# 08_-PumpDriverUnit.net
KiCad netlist of a schematic drawn in Altium Designer
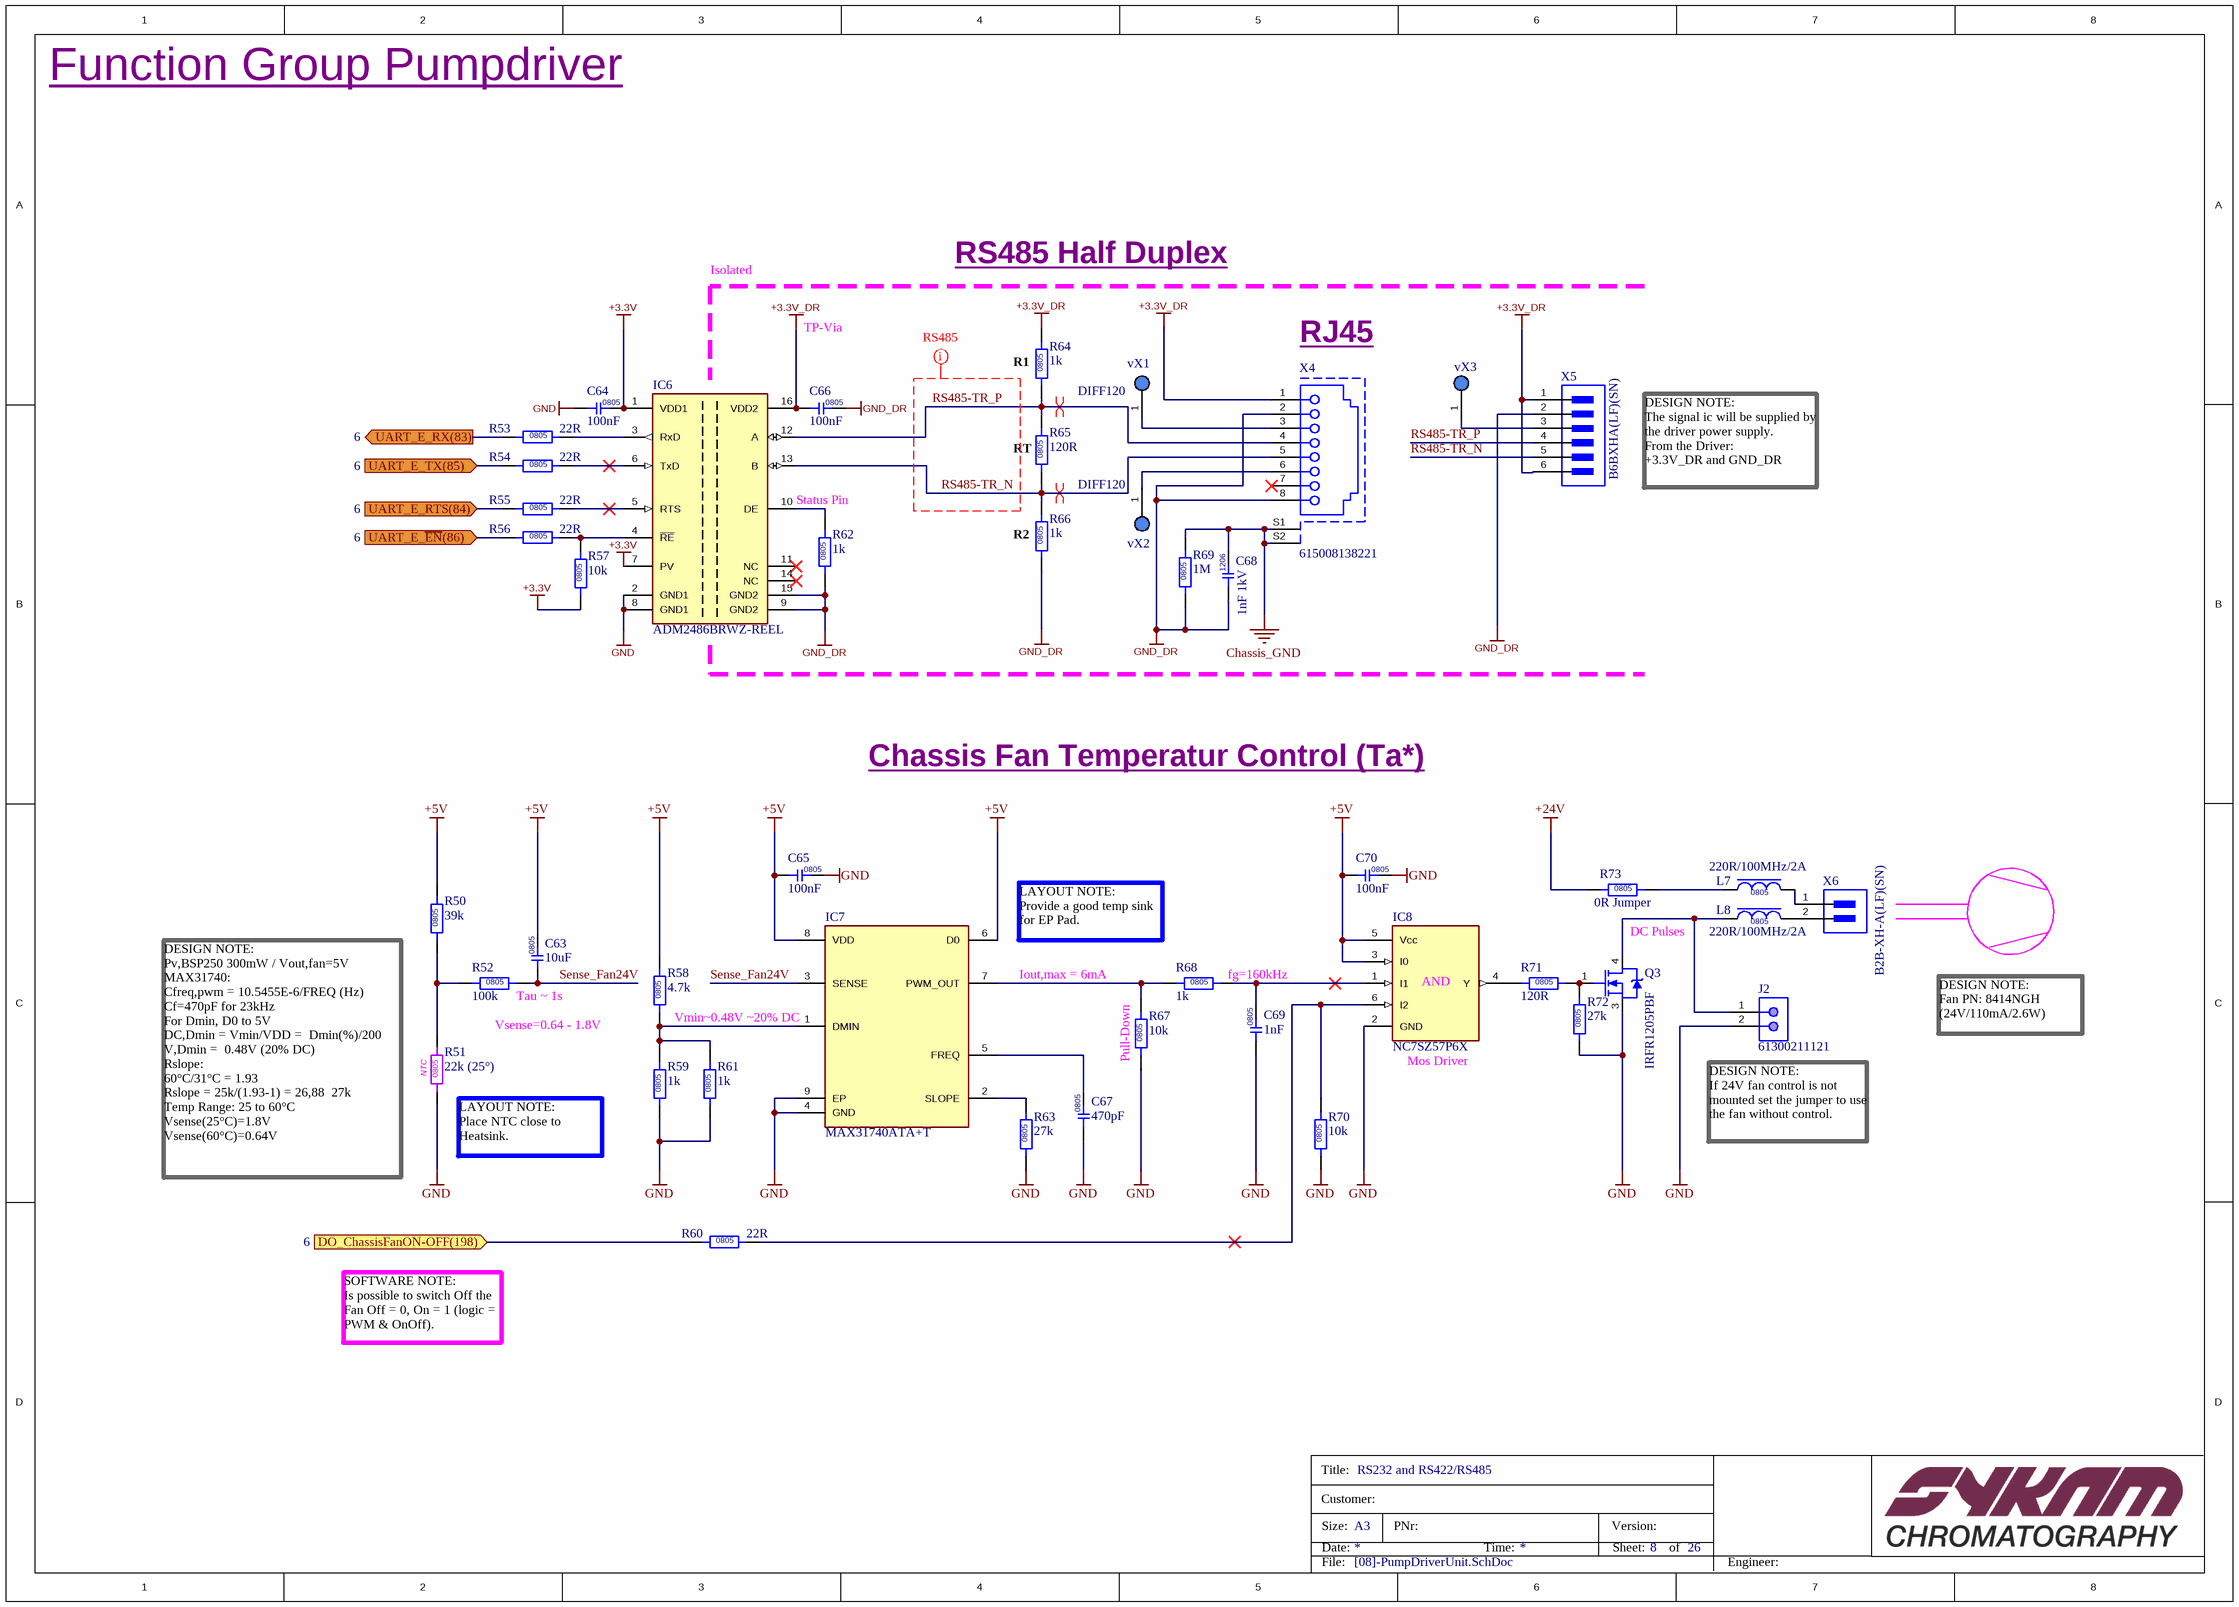
[diagram p0: [08]-PumpDriverUnit.SchDoc]

(export (version "E")
  (design (tool "Eeschema 10.0.6"))
  (components
    (comp (ref "C63")
      (value "10uF")
      (footprint "C0805")
      (description "0805 10 uF 50 V ±20% Tolerance X5R Multilayer Ceramic Capacitor")
      (fields
        (field (name "MANUFACTURER") "Murata")
        (field (name "MANUFACTURER PART NUMBER") "GRM21BR6YA106ME43L")
      )
      (libsource (lib "ToradexMainBoard-V0I1") (part "C_10uF_GRM21BR6YA106ME43L"))
    )
    (comp (ref "C64")
      (value "100nF")
      (footprint "C0805")
      (description "CAP CER 0.1UF 50V X7R 0805")
      (fields (field (name "MANUFACTURER PART NUMBER") "CC0805KRX7R9BB104") (field (name "TOLERANCE") "10%"))
      (libsource (lib "Sykam-LagerBauteile1") (part "C_100nF_CC0805KRX7R9BB104"))
    )
    (comp (ref "C65")
      (value "100nF")
      (footprint "C0805")
      (description "CAP CER 0.1UF 50V X7R 0805")
      (fields
        (field (name "MANUFACTURER PART NUMBER") "CC0805KRX7R9BB104")
        (field (name "TOLERANCE") "10%")
        (field (name "PCBCHECKED") "initials after Checked")
        (field (name "SCHCHECKED") "Initials after checked")
      )
      (libsource (lib "ToradexMainBoard-V0I1") (part "C_100nF_CC0805KRX7R9BB104"))
    )
    (comp (ref "C66")
      (value "100nF")
      (footprint "C0805")
      (description "CAP CER 0.1UF 50V X7R 0805")
      (fields (field (name "MANUFACTURER PART NUMBER") "CC0805KRX7R9BB104") (field (name "TOLERANCE") "10%"))
      (libsource (lib "Sykam-LagerBauteile1") (part "C_100nF_CC0805KRX7R9BB104"))
    )
    (comp (ref "C67")
      (value "470pF")
      (footprint "C0805")
      (fields
        (field (name "MANUFACTURER") "Kyocera AVX")
        (field (name "MANUFACTURER PART NUMBER") "08051A471JAT2A")
        (field (name "TOLERANCE") "5%")
      )
      (libsource (lib "ToradexMainBoard-V0I1") (part "C_470pF_08051A471JAT2A"))
    )
    (comp (ref "C68")
      (value "1nF 1kV")
      (footprint "C1206")
      (description "CAP CER 1000PF 1KV X7S 1206")
      (fields
        (field (name "MANUFACTURER") "TDK")
        (field (name "MANUFACTURER PART NUMBER") "CGA5F1X7S3A102M085AE")
      )
      (libsource (lib "Sykam-LagerBauteile1-B") (part "C_1nF-1kV-CGA5F1X7S3A102M085AE"))
    )
    (comp (ref "C69")
      (value "1nF")
      (footprint "C0805")
      (description "Multilayer Ceramic Capacitors MLCC - SMD/SMT 50volts 1000pF X7R 10%")
      (fields
        (field (name "MANUFACTURER") "KEMET")
        (field (name "MANUFACTURER PART NUMBER") "C0805C102K5RAC7411")
      )
      (libsource (lib "ToradexMainBoard-V0I1") (part "C_1nF_C0805C102K5RAC7411"))
    )
    (comp (ref "C70")
      (value "100nF")
      (footprint "C0805")
      (description "CAP CER 0.1UF 50V X7R 0805")
      (fields
        (field (name "MANUFACTURER PART NUMBER") "CC0805KRX7R9BB104")
        (field (name "TOLERANCE") "10%")
        (field (name "PCBCHECKED") "initials after Checked")
        (field (name "SCHCHECKED") "Initials after checked")
      )
      (libsource (lib "ToradexMainBoard-V0I1") (part "C_100nF_CC0805KRX7R9BB104"))
    )
    (comp (ref "IC6")
      (value "ADM2486BRWZ-REEL")
      (footprint "ADM2486_SOIC16W")
      (description "Single Transmitter/Receiver RS-485 16-Pin SOIC W T/R")
      (fields (field (name "MANUFACTURER") "Analog Devices"))
      (libsource (lib "ToradexMainBoard-V0I1") (part "IC_ADM2486BRWZ-REEL"))
    )
    (comp (ref "IC7")
      (value "MAX31740ATA+T")
      (footprint "TDFN-MN8")
      (description "Fan Motor Speed Controller 3V to 5.5V 8-Pin TDFN EP T/R")
      (fields (field (name "MANUFACTURER") "Maxim"))
      (libsource (lib "ToradexMainBoard-V0I1") (part "IC_MAX31740ATA+T"))
    )
    (comp (ref "IC8")
      (value "NC7SZ57P6X")
      (footprint "NC7SZ57P6X")
      (fields
        (field (name "MANUFACTURER") "ON Semiconductor / Fairchild")
        (field (name "PCBCHECKED") "initials after Checked")
        (field (name "SCHCHECKED") "Initials after checked")
      )
      (libsource (lib "ToradexMainBoard-V0I1") (part "IC_NC7SZ57P6X"))
    )
    (comp (ref "J2")
      (value "61300211121")
      (footprint "CON-61300211121_Jumper-2p")
      (fields (field (name "MANUFACTURER") "Wurth Electronics"))
      (libsource (lib "ToradexMainBoard-V0I1") (part "CON_J_61300211121"))
    )
    (comp (ref "L7")
      (value "220R/100MHz/2A")
      (footprint "L0805")
      (description "Ferrite Beads Multi-Layer 220Ohm 25% 100MHz 2A 45mOhm DCR 0805 Paper T/R")
      (fields
        (field (name "MANUFACTURER PART NUMBER") "BLM21PG221SN1D")
        (field (name "TOLERANCE") "25%")
        (field (name "PCBCHECKED") "initials after Checked")
        (field (name "SCHCHECKED") "Initials after checked")
      )
      (libsource (lib "ToradexMainBoard-V0I1") (part "L_BLM21PG221SN1D"))
    )
    (comp (ref "L8")
      (value "220R/100MHz/2A")
      (footprint "L0805")
      (description "Ferrite Beads Multi-Layer 220Ohm 25% 100MHz 2A 45mOhm DCR 0805 Paper T/R")
      (fields
        (field (name "MANUFACTURER PART NUMBER") "BLM21PG221SN1D")
        (field (name "TOLERANCE") "25%")
        (field (name "PCBCHECKED") "initials after Checked")
        (field (name "SCHCHECKED") "Initials after checked")
      )
      (libsource (lib "ToradexMainBoard-V0I1") (part "L_BLM21PG221SN1D"))
    )
    (comp (ref "Q3")
      (value "IRFR1205PBF")
      (footprint "NMOS-TO-252AA-3_M")
      (description "HEXFET(R) Power MOSFET, 55 V, 44 A, 27 mOhm, -55 to 175 degC, 3-Pin DPAK (TO-252AA), RoHS, Tube")
      (fields (field (name "MANUFACTURER") "International Rectifier"))
      (libsource (lib "ToradexMainBoard-V0I1") (part "Q_NMOS-IRFR1205PBF"))
    )
    (comp (ref "R50")
      (value "39k")
      (footprint "R0805")
      (description "Res Thick Film 0805 39K Ohm 1% 0.125W(1/8W) ±100ppm/C Pad SMD Automotive T/R")
      (fields
        (field (name "MANUFACTURER") "Vishay")
        (field (name "MANUFACTURER PART NUMBER") "CRCW080539K0FKEA")
      )
      (libsource (lib "ToradexMainBoard-V0I1") (part "R_39k_CRCW080539K0FKEA"))
    )
    (comp (ref "R51")
      (value "22k (25°)")
      (footprint "R_NTC-PTC-0805")
      (description "Thermistor NTC 22K Ohm 5% 2-Pin 0805 Surface Mount Solder Pad 4455K Blister T/R")
      (fields
        (field (name "MANUFACTURER") "TDK EPCOS")
        (field (name "MANUFACTURER PART NUMBER") "B57471V2223J062")
      )
      (libsource (lib "ToradexMainBoard-V0I1") (part "R_NTC_22k_B57471V2223J062"))
    )
    (comp (ref "R52")
      (value "100k")
      (footprint "R0805")
      (description "RES SMD 100K OHM 1% 1/8W 0805")
      (fields
        (field (name "MANUFACTURER PART NUMBER") "RC0805FR-07100KL")
        (field (name "TOLERANCE") "1%")
        (field (name "PCBCHECKED") "initials after Checked")
        (field (name "SCHCHECKED") "Initials after checked")
      )
      (libsource (lib "ToradexMainBoard-V0I1") (part "R_100k_RC0805FR-07100KL"))
    )
    (comp (ref "R53")
      (value "22R")
      (footprint "R0805")
      (description "RES SMD 22 OHM 1% 1/8W 0805")
      (fields (field (name "MANUFACTURER PART NUMBER") "RC0805FR-0722RL") (field (name "TOLERANCE") "1%"))
      (libsource (lib "Sykam-LagerBauteile1") (part "R_22R_RC0805FR-0722RL"))
    )
    (comp (ref "R54")
      (value "22R")
      (footprint "R0805")
      (description "RES SMD 22 OHM 1% 1/8W 0805")
      (fields (field (name "MANUFACTURER PART NUMBER") "RC0805FR-0722RL") (field (name "TOLERANCE") "1%"))
      (libsource (lib "Sykam-LagerBauteile1") (part "R_22R_RC0805FR-0722RL"))
    )
    (comp (ref "R55")
      (value "22R")
      (footprint "R0805")
      (description "RES SMD 22 OHM 1% 1/8W 0805")
      (fields (field (name "MANUFACTURER PART NUMBER") "RC0805FR-0722RL") (field (name "TOLERANCE") "1%"))
      (libsource (lib "Sykam-LagerBauteile1") (part "R_22R_RC0805FR-0722RL"))
    )
    (comp (ref "R56")
      (value "22R")
      (footprint "R0805")
      (description "RES SMD 22 OHM 1% 1/8W 0805")
      (fields (field (name "MANUFACTURER PART NUMBER") "RC0805FR-0722RL") (field (name "TOLERANCE") "1%"))
      (libsource (lib "Sykam-LagerBauteile1") (part "R_22R_RC0805FR-0722RL"))
    )
    (comp (ref "R57")
      (value "10k")
      (footprint "R0805")
      (description "RES SMD 10K OHM 1% 1/8W 0805")
      (fields
        (field (name "MANUFACTURER PART NUMBER") "RC0805FR-0710KL")
        (field (name "TOLERANCE") "1%")
        (field (name "PCBCHECKED") "initials after Checked")
        (field (name "SCHCHECKED") "Initials after checked")
      )
      (libsource (lib "ToradexMainBoard-V0I1") (part "R_10k_RC0805FR-0710KL"))
    )
    (comp (ref "R58")
      (value "4.7k")
      (footprint "R0805")
      (fields
        (field (name "MANUFACTURER PART NUMBER") "RC0805FR-074K7L")
        (field (name "TOLERANCE") "1%")
        (field (name "MANUFACTURER") "Yageo")
        (field (name "PCBCHECKED") "initials after Checked")
        (field (name "SCHCHECKED") "Initials after checked")
      )
      (libsource (lib "ToradexMainBoard-V0I1") (part "R_4k7_RC0805FR-074K7L"))
    )
    (comp (ref "R59")
      (value "1k")
      (footprint "R0805")
      (fields
        (field (name "MANUFACTURER PART NUMBER") "RC0805FR-071KL")
        (field (name "TOLERANCE") "1%")
        (field (name "MANUFACTURER") "Yageo")
        (field (name "PCBCHECKED") "initials after Checked")
        (field (name "SCHCHECKED") "Initials after checked")
      )
      (libsource (lib "ToradexMainBoard-V0I1") (part "R_1k_RC0805FR-071KL"))
    )
    (comp (ref "R60")
      (value "22R")
      (footprint "R0805")
      (description "RES SMD 22 OHM 1% 1/8W 0805")
      (fields
        (field (name "MANUFACTURER PART NUMBER") "RC0805FR-0722RL")
        (field (name "TOLERANCE") "1%")
        (field (name "PCBCHECKED") "initials after Checked")
        (field (name "SCHCHECKED") "Initials after checked")
      )
      (libsource (lib "Sykam-LagerBauteile1-B") (part "R_22R_RC0805FR-0722RL"))
    )
    (comp (ref "R61")
      (value "1k")
      (footprint "R0805")
      (fields
        (field (name "MANUFACTURER PART NUMBER") "RC0805FR-071KL")
        (field (name "TOLERANCE") "1%")
        (field (name "MANUFACTURER") "Yageo")
        (field (name "PCBCHECKED") "initials after Checked")
        (field (name "SCHCHECKED") "Initials after checked")
      )
      (libsource (lib "ToradexMainBoard-V0I1") (part "R_1k_RC0805FR-071KL"))
    )
    (comp (ref "R62")
      (value "1k")
      (footprint "R0805")
      (fields
        (field (name "MANUFACTURER PART NUMBER") "RC0805FR-071KL")
        (field (name "TOLERANCE") "1%")
        (field (name "MANUFACTURER") "Yageo")
      )
      (libsource (lib "Sykam-LagerBauteile1") (part "R_1k_RC0805FR-071KL"))
    )
    (comp (ref "R63")
      (value "27k")
      (footprint "R0805")
      (description "Surface Mount Thick Film Resistor, RC Series, 27 kohm, 125 mW, - 1%, 150 V, 0805 [2012 Metric]")
      (fields
        (field (name "MANUFACTURER") "Yageo")
        (field (name "MANUFACTURER PART NUMBER") "RC0805FR-0727KL")
      )
      (libsource (lib "ToradexMainBoard-V0I1") (part "R_27k_RC0805FR-0727KL"))
    )
    (comp (ref "R64")
      (value "1k")
      (footprint "R0805")
      (fields
        (field (name "MANUFACTURER PART NUMBER") "RC0805FR-071KL")
        (field (name "TOLERANCE") "1%")
        (field (name "MANUFACTURER") "Yageo")
      )
      (libsource (lib "Sykam-LagerBauteile1") (part "R_1k_RC0805FR-071KL"))
    )
    (comp (ref "R65")
      (value "120R")
      (footprint "R0805")
      (description "RES SMD 120 OHM 1% 1/8W 0805")
      (fields (field (name "MANUFACTURER PART NUMBER") "RC0805FR-07120RL") (field (name "TOLERANCE") "1%"))
      (libsource (lib "Sykam-LagerBauteile1") (part "R_120R_RC0805FR-07120RL"))
    )
    (comp (ref "R66")
      (value "1k")
      (footprint "R0805")
      (fields
        (field (name "MANUFACTURER PART NUMBER") "RC0805FR-071KL")
        (field (name "TOLERANCE") "1%")
        (field (name "MANUFACTURER") "Yageo")
      )
      (libsource (lib "Sykam-LagerBauteile1") (part "R_1k_RC0805FR-071KL"))
    )
    (comp (ref "R67")
      (value "10k")
      (footprint "R0805")
      (description "RES SMD 10K OHM 1% 1/8W 0805")
      (fields
        (field (name "MANUFACTURER PART NUMBER") "RC0805FR-0710KL")
        (field (name "TOLERANCE") "1%")
        (field (name "PCBCHECKED") "initials after Checked")
        (field (name "SCHCHECKED") "Initials after checked")
      )
      (libsource (lib "ToradexMainBoard-V0I1") (part "R_10k_RC0805FR-0710KL"))
    )
    (comp (ref "R68")
      (value "1k")
      (footprint "R0805")
      (fields
        (field (name "MANUFACTURER PART NUMBER") "RC0805FR-071KL")
        (field (name "TOLERANCE") "1%")
        (field (name "MANUFACTURER") "Yageo")
        (field (name "PCBCHECKED") "initials after Checked")
        (field (name "SCHCHECKED") "Initials after checked")
      )
      (libsource (lib "ToradexMainBoard-V0I1") (part "R_1k_RC0805FR-071KL"))
    )
    (comp (ref "R69")
      (value "1M")
      (footprint "R0805")
      (description "Res Thick Film 0805 1M Ohm 1% 0.125W(1/8W) ±100ppm/C Epoxy SMD T/R")
      (fields
        (field (name "MANUFACTURER") "Yageo")
        (field (name "MANUFACTURER PART NUMBER") "RC0805FR-071ML")
      )
      (libsource (lib "Sykam-LagerBauteile1-B") (part "R_1M_RC0805FR-071ML"))
    )
    (comp (ref "R70")
      (value "10k")
      (footprint "R0805")
      (description "RES SMD 10K OHM 1% 1/8W 0805")
      (fields
        (field (name "MANUFACTURER PART NUMBER") "RC0805FR-0710KL")
        (field (name "TOLERANCE") "1%")
        (field (name "PCBCHECKED") "initials after Checked")
        (field (name "SCHCHECKED") "Initials after checked")
      )
      (libsource (lib "ToradexMainBoard-V0I1") (part "R_10k_RC0805FR-0710KL"))
    )
    (comp (ref "R71")
      (value "120R")
      (footprint "R0805")
      (description "RES SMD 120 OHM 1% 1/8W 0805")
      (fields
        (field (name "MANUFACTURER PART NUMBER") "RC0805FR-07120RL")
        (field (name "TOLERANCE") "1%")
        (field (name "PCBCHECKED") "initials after Checked")
        (field (name "SCHCHECKED") "Initials after checked")
      )
      (libsource (lib "ToradexMainBoard-V0I1") (part "R_120R_RC0805FR-07120RL"))
    )
    (comp (ref "R72")
      (value "27k")
      (footprint "R0805")
      (description "Surface Mount Thick Film Resistor, RC Series, 27 kohm, 125 mW, - 1%, 150 V, 0805 [2012 Metric]")
      (fields
        (field (name "MANUFACTURER") "Yageo")
        (field (name "MANUFACTURER PART NUMBER") "RC0805FR-0727KL")
      )
      (libsource (lib "ToradexMainBoard-V0I1") (part "R_27k_RC0805FR-0727KL"))
    )
    (comp (ref "R73")
      (value "0R Jumper")
      (footprint "R0805")
      (fields
        (field (name "MANUFACTURER PART NUMBER") "RMCF0805ZT0R00")
        (field (name "MANUFACTURER") "Stackpole Electronics")
        (field (name "PCBCHECKED") "initials after Checked")
        (field (name "SCHCHECKED") "Initials after checked")
      )
      (libsource (lib "ToradexMainBoard-V0I1") (part "R_0R_RMCF0805ZT0R00"))
    )
    (comp (ref "vX1")
      (value "Reserve Contact Via 0.5mm")
      (footprint "ReseveContact")
      (description "Via Reserve Kontakt")
      (libsource (lib "Sykam-Mech1") (part "Reserve-Kontakt-T/B-Layer"))
    )
    (comp (ref "vX2")
      (value "Reserve Contact Via 0.5mm")
      (footprint "ReseveContact")
      (description "Via Reserve Kontakt")
      (libsource (lib "Sykam-Mech1") (part "Reserve-Kontakt-T/B-Layer"))
    )
    (comp (ref "vX3")
      (value "Reserve Contact Via 0.5mm")
      (footprint "ReseveContact")
      (description "Via Reserve Kontakt")
      (libsource (lib "Sykam-Mech1") (part "Reserve-Kontakt-T/B-Layer"))
    )
    (comp (ref "X4")
      (value "615008138221")
      (footprint "RJ45-V-615008138221")
      (description "WURTH ELEKTRONIK - 615008138221 - JACK, RJ45, VERT, 8P8C, SHIELDED")
      (fields (field (name "MANUFACTURER") "Wurth Electronics"))
      (libsource (lib "Evaluation Board") (part "CON-615008138221"))
    )
    (comp (ref "X5")
      (value "B6BXHA(LF)(SN)")
      (footprint "B6BXHA(LF)(SN)")
      (description "CONN HEADER VERT 6POS 2.5MM")
      (fields (field (name "MANUFACTURER") "JST"))
      (libsource (lib "Sykam-LagerBauteile1") (part "CON_6pol_B6BXHA(LF)(SN)"))
    )
    (comp (ref "X6")
      (value "B2B-XH-A(LF)(SN)")
      (footprint "CON_2p_JST-B2B-XH-A_V")
      (description "Conn Shrouded Header (4 Sides) HDR 2 POS 2.5mm Solder ST Thru-Hole Box")
      (fields (field (name "MANUFACTURER") "JST"))
      (libsource (lib "ToradexMainBoard-V0I1") (part "CON_2p_B2B-XH-A(LF)(SN)"))
    )
  )
  (nets
    (net (code "1") (name "+3.3V") (class "Default")
      (node (ref "C64") (pin "2") (pinfunction "2_2") (pintype "passive"))
      (node (ref "IC6") (pin "1") (pinfunction "VDD1_1") (pintype "power_in"))
      (node (ref "IC6") (pin "7") (pinfunction "PV_7") (pintype "passive"))
      (node (ref "R57") (pin "1") (pinfunction "1_1") (pintype "passive"))
    )
    (net (code "2") (name "+3.3V_DR") (class "Default")
      (node (ref "C66") (pin "1") (pinfunction "1_1") (pintype "passive"))
      (node (ref "IC6") (pin "16") (pinfunction "VDD2_16") (pintype "power_in"))
      (node (ref "R64") (pin "2") (pinfunction "2_2") (pintype "passive"))
      (node (ref "X4") (pin "1") (pinfunction "1_1") (pintype "passive"))
      (node (ref "X5") (pin "1") (pintype "passive"))
      (node (ref "X5") (pin "6") (pintype "passive"))
    )
    (net (code "3") (name "+5V") (class "Default")
      (node (ref "C63") (pin "2") (pinfunction "2_2") (pintype "passive"))
      (node (ref "C65") (pin "1") (pinfunction "1_1") (pintype "passive"))
      (node (ref "C70") (pin "1") (pinfunction "1_1") (pintype "passive"))
      (node (ref "IC7") (pin "6") (pinfunction "D0_6") (pintype "power_in"))
      (node (ref "IC7") (pin "8") (pinfunction "VDD_8") (pintype "power_in"))
      (node (ref "IC8") (pin "3") (pinfunction "I0_3") (pintype "input"))
      (node (ref "IC8") (pin "5") (pinfunction "Vcc_5") (pintype "passive"))
      (node (ref "R50") (pin "2") (pinfunction "2_2") (pintype "passive"))
      (node (ref "R58") (pin "2") (pinfunction "2_2") (pintype "passive"))
    )
    (net (code "4") (name "+24V") (class "Default")
      (node (ref "R73") (pin "1") (pinfunction "1_1") (pintype "passive"))
    )
    (net (code "5") (name "/DO_ChassisFanON-OFF(198)") (class "Default")
      (node (ref "R60") (pin "1") (pinfunction "1_1") (pintype "passive"))
    )
    (net (code "6") (name "/RS485-TR_N") (class "Default")
      (node (ref "IC6") (pin "13") (pinfunction "B_13") (pintype "bidirectional"))
      (node (ref "R65") (pin "1") (pinfunction "1_1") (pintype "passive"))
      (node (ref "R66") (pin "2") (pinfunction "2_2") (pintype "passive"))
      (node (ref "X4") (pin "5") (pinfunction "5_5") (pintype "passive"))
      (node (ref "X5") (pin "5") (pintype "passive"))
    )
    (net (code "7") (name "/RS485-TR_P") (class "Default")
      (node (ref "IC6") (pin "12") (pinfunction "A_12") (pintype "bidirectional"))
      (node (ref "R64") (pin "1") (pinfunction "1_1") (pintype "passive"))
      (node (ref "R65") (pin "2") (pinfunction "2_2") (pintype "passive"))
      (node (ref "X4") (pin "4") (pinfunction "4_4") (pintype "passive"))
      (node (ref "X5") (pin "4") (pintype "passive"))
    )
    (net (code "8") (name "/Sense_Fan24V") (class "Default")
      (node (ref "C63") (pin "1") (pinfunction "1_1") (pintype "passive"))
      (node (ref "IC7") (pin "3") (pinfunction "SENSE_3") (pintype "power_in"))
      (node (ref "R52") (pin "2") (pinfunction "2_2") (pintype "passive"))
    )
    (net (code "9") (name "/UART_E_RTS(84)") (class "Default")
      (node (ref "R55") (pin "1") (pinfunction "1_1") (pintype "passive"))
    )
    (net (code "10") (name "/UART_E_RX(83)") (class "Default")
      (node (ref "R53") (pin "1") (pinfunction "1_1") (pintype "passive"))
    )
    (net (code "11") (name "/UART_E_TX(85)") (class "Default")
      (node (ref "R54") (pin "1") (pinfunction "1_1") (pintype "passive"))
    )
    (net (code "12") (name "/UART_E_~{EN}(86)") (class "Default")
      (node (ref "R56") (pin "1") (pinfunction "1_1") (pintype "passive"))
    )
    (net (code "13") (name "Chassis_GND") (class "Default")
      (node (ref "C68") (pin "2") (pinfunction "2_2") (pintype "passive"))
      (node (ref "R69") (pin "2") (pinfunction "2_2") (pintype "passive"))
      (node (ref "X4") (pin "S1") (pinfunction "S1_S1") (pintype "passive"))
      (node (ref "X4") (pin "S2") (pinfunction "S2_S2") (pintype "passive"))
    )
    (net (code "14") (name "GND") (class "Default")
      (node (ref "C64") (pin "1") (pinfunction "1_1") (pintype "passive"))
      (node (ref "C65") (pin "2") (pinfunction "2_2") (pintype "passive"))
      (node (ref "C67") (pin "1") (pinfunction "1_1") (pintype "passive"))
      (node (ref "C69") (pin "1") (pinfunction "1_1") (pintype "passive"))
      (node (ref "C70") (pin "2") (pinfunction "2_2") (pintype "passive"))
      (node (ref "IC6") (pin "2") (pinfunction "GND1_2") (pintype "power_in"))
      (node (ref "IC6") (pin "8") (pinfunction "GND1_8") (pintype "power_in"))
      (node (ref "IC7") (pin "4") (pinfunction "GND_4") (pintype "power_in"))
      (node (ref "IC7") (pin "9") (pinfunction "EP_9") (pintype "power_in"))
      (node (ref "IC8") (pin "2") (pinfunction "GND_2") (pintype "passive"))
      (node (ref "J2") (pin "2") (pinfunction "2_2") (pintype "passive"))
      (node (ref "Q3") (pin "3") (pinfunction "S_3") (pintype "passive"))
      (node (ref "R51") (pin "1") (pinfunction "1_1") (pintype "passive"))
      (node (ref "R59") (pin "1") (pinfunction "1_1") (pintype "passive"))
      (node (ref "R61") (pin "1") (pinfunction "1_1") (pintype "passive"))
      (node (ref "R63") (pin "1") (pinfunction "1_1") (pintype "passive"))
      (node (ref "R67") (pin "1") (pinfunction "1_1") (pintype "passive"))
      (node (ref "R70") (pin "1") (pinfunction "1_1") (pintype "passive"))
      (node (ref "R72") (pin "1") (pinfunction "1_1") (pintype "passive"))
    )
    (net (code "15") (name "GND_DR") (class "Default")
      (node (ref "C66") (pin "2") (pinfunction "2_2") (pintype "passive"))
      (node (ref "C68") (pin "1") (pinfunction "1_1") (pintype "passive"))
      (node (ref "IC6") (pin "15") (pinfunction "GND2_15") (pintype "power_in"))
      (node (ref "IC6") (pin "9") (pinfunction "GND2_9") (pintype "power_in"))
      (node (ref "R62") (pin "1") (pinfunction "1_1") (pintype "passive"))
      (node (ref "R66") (pin "1") (pinfunction "1_1") (pintype "passive"))
      (node (ref "R69") (pin "1") (pinfunction "1_1") (pintype "passive"))
      (node (ref "X4") (pin "2") (pinfunction "2_2") (pintype "passive"))
      (node (ref "X4") (pin "8") (pinfunction "8_8") (pintype "passive"))
      (node (ref "X5") (pin "2") (pintype "passive"))
    )
    (net (code "16") (name "Net-(IC6-DE)") (class "Default")
      (node (ref "IC6") (pin "10") (pinfunction "DE_10") (pintype "passive"))
      (node (ref "R62") (pin "2") (pinfunction "2_2") (pintype "passive"))
    )
    (net (code "17") (name "Net-(IC6-RTS)") (class "Default")
      (node (ref "IC6") (pin "5") (pinfunction "RTS_5") (pintype "input"))
      (node (ref "R55") (pin "2") (pinfunction "2_2") (pintype "passive"))
    )
    (net (code "18") (name "Net-(IC6-RxD)") (class "Default")
      (node (ref "IC6") (pin "3") (pinfunction "RxD_3") (pintype "output"))
      (node (ref "R53") (pin "2") (pinfunction "2_2") (pintype "passive"))
    )
    (net (code "19") (name "Net-(IC6-TxD)") (class "Default")
      (node (ref "IC6") (pin "6") (pinfunction "TxD_6") (pintype "input"))
      (node (ref "R54") (pin "2") (pinfunction "2_2") (pintype "passive"))
    )
    (net (code "20") (name "Net-(IC6-~{RE})") (class "Default")
      (node (ref "IC6") (pin "4") (pinfunction "~{RE}_4") (pintype "passive"))
      (node (ref "R56") (pin "2") (pinfunction "2_2") (pintype "passive"))
      (node (ref "R57") (pin "2") (pinfunction "2_2") (pintype "passive"))
    )
    (net (code "21") (name "Net-(IC7-DMIN)") (class "Default")
      (node (ref "IC7") (pin "1") (pinfunction "DMIN_1") (pintype "power_in"))
      (node (ref "R58") (pin "1") (pinfunction "1_1") (pintype "passive"))
      (node (ref "R59") (pin "2") (pinfunction "2_2") (pintype "passive"))
      (node (ref "R61") (pin "2") (pinfunction "2_2") (pintype "passive"))
    )
    (net (code "22") (name "Net-(IC7-FREQ)") (class "Default")
      (node (ref "C67") (pin "2") (pinfunction "2_2") (pintype "passive"))
      (node (ref "IC7") (pin "5") (pinfunction "FREQ_5") (pintype "power_in"))
    )
    (net (code "23") (name "Net-(IC7-PWM_OUT)") (class "Default")
      (node (ref "IC7") (pin "7") (pinfunction "PWM_OUT_7") (pintype "power_in"))
      (node (ref "R67") (pin "2") (pinfunction "2_2") (pintype "passive"))
      (node (ref "R68") (pin "1") (pinfunction "1_1") (pintype "passive"))
    )
    (net (code "24") (name "Net-(IC7-SLOPE)") (class "Default")
      (node (ref "IC7") (pin "2") (pinfunction "SLOPE_2") (pintype "power_in"))
      (node (ref "R63") (pin "2") (pinfunction "2_2") (pintype "passive"))
    )
    (net (code "25") (name "Net-(IC8-I1)") (class "Default")
      (node (ref "C69") (pin "2") (pinfunction "2_2") (pintype "passive"))
      (node (ref "IC8") (pin "1") (pinfunction "I1_1") (pintype "input"))
      (node (ref "R68") (pin "2") (pinfunction "2_2") (pintype "passive"))
    )
    (net (code "26") (name "Net-(IC8-I2)") (class "Default")
      (node (ref "IC8") (pin "6") (pinfunction "I2_6") (pintype "input"))
      (node (ref "R60") (pin "2") (pinfunction "2_2") (pintype "passive"))
      (node (ref "R70") (pin "2") (pinfunction "2_2") (pintype "passive"))
    )
    (net (code "27") (name "Net-(IC8-Y)") (class "Default")
      (node (ref "IC8") (pin "4") (pinfunction "Y_4") (pintype "output"))
      (node (ref "R71") (pin "1") (pinfunction "1_1") (pintype "passive"))
    )
    (net (code "28") (name "Net-(L7-Pad1)") (class "Default")
      (node (ref "L7") (pin "1") (pinfunction "1_1") (pintype "passive"))
      (node (ref "R73") (pin "2") (pinfunction "2_2") (pintype "passive"))
    )
    (net (code "29") (name "Net-(L7-Pad2)") (class "Default")
      (node (ref "L7") (pin "2") (pinfunction "2_2") (pintype "passive"))
      (node (ref "X6") (pin "1") (pintype "passive"))
    )
    (net (code "30") (name "Net-(L8-Pad2)") (class "Default")
      (node (ref "L8") (pin "2") (pinfunction "2_2") (pintype "passive"))
      (node (ref "X6") (pin "2") (pintype "passive"))
    )
    (net (code "31") (name "Net-(Q3-D)") (class "Default")
      (node (ref "J2") (pin "1") (pinfunction "1_1") (pintype "passive"))
      (node (ref "L8") (pin "1") (pinfunction "1_1") (pintype "passive"))
      (node (ref "Q3") (pin "4") (pinfunction "D_4") (pintype "passive"))
    )
    (net (code "32") (name "Net-(Q3-G)") (class "Default")
      (node (ref "Q3") (pin "1") (pinfunction "G_1") (pintype "passive"))
      (node (ref "R71") (pin "2") (pinfunction "2_2") (pintype "passive"))
      (node (ref "R72") (pin "2") (pinfunction "2_2") (pintype "passive"))
    )
    (net (code "33") (name "Net-(R50-Pad1)") (class "Default")
      (node (ref "R50") (pin "1") (pinfunction "1_1") (pintype "passive"))
      (node (ref "R51") (pin "2") (pinfunction "2_2") (pintype "passive"))
      (node (ref "R52") (pin "1") (pinfunction "1_1") (pintype "passive"))
    )
    (net (code "34") (name "Net-(X4-Pad3)") (class "Default")
      (node (ref "X4") (pin "3") (pinfunction "3_3") (pintype "passive"))
      (node (ref "vX1") (pin "1") (pintype "passive"))
    )
    (net (code "35") (name "Net-(X4-Pad6)") (class "Default")
      (node (ref "X4") (pin "6") (pinfunction "6_6") (pintype "passive"))
      (node (ref "vX2") (pin "1") (pintype "passive"))
    )
    (net (code "36") (name "Net-(X5-Pad3)") (class "Default")
      (node (ref "X5") (pin "3") (pintype "passive"))
      (node (ref "vX3") (pin "1") (pintype "passive"))
    )
    (net (code "37") (name "unconnected-(IC6-NC-Pad11)") (class "Default")
      (node (ref "IC6") (pin "11") (pinfunction "NC_11") (pintype "passive+no_connect"))
    )
    (net (code "38") (name "unconnected-(IC6-NC-Pad14)") (class "Default")
      (node (ref "IC6") (pin "14") (pinfunction "NC_14") (pintype "tri_state+no_connect"))
    )
    (net (code "39") (name "unconnected-(X4-Pad7)") (class "Default")
      (node (ref "X4") (pin "7") (pinfunction "7_7") (pintype "passive+no_connect"))
    )
  )
)
